# SolarSenseBoard.net
KiCad netlist of a schematic drawn in Altium Designer
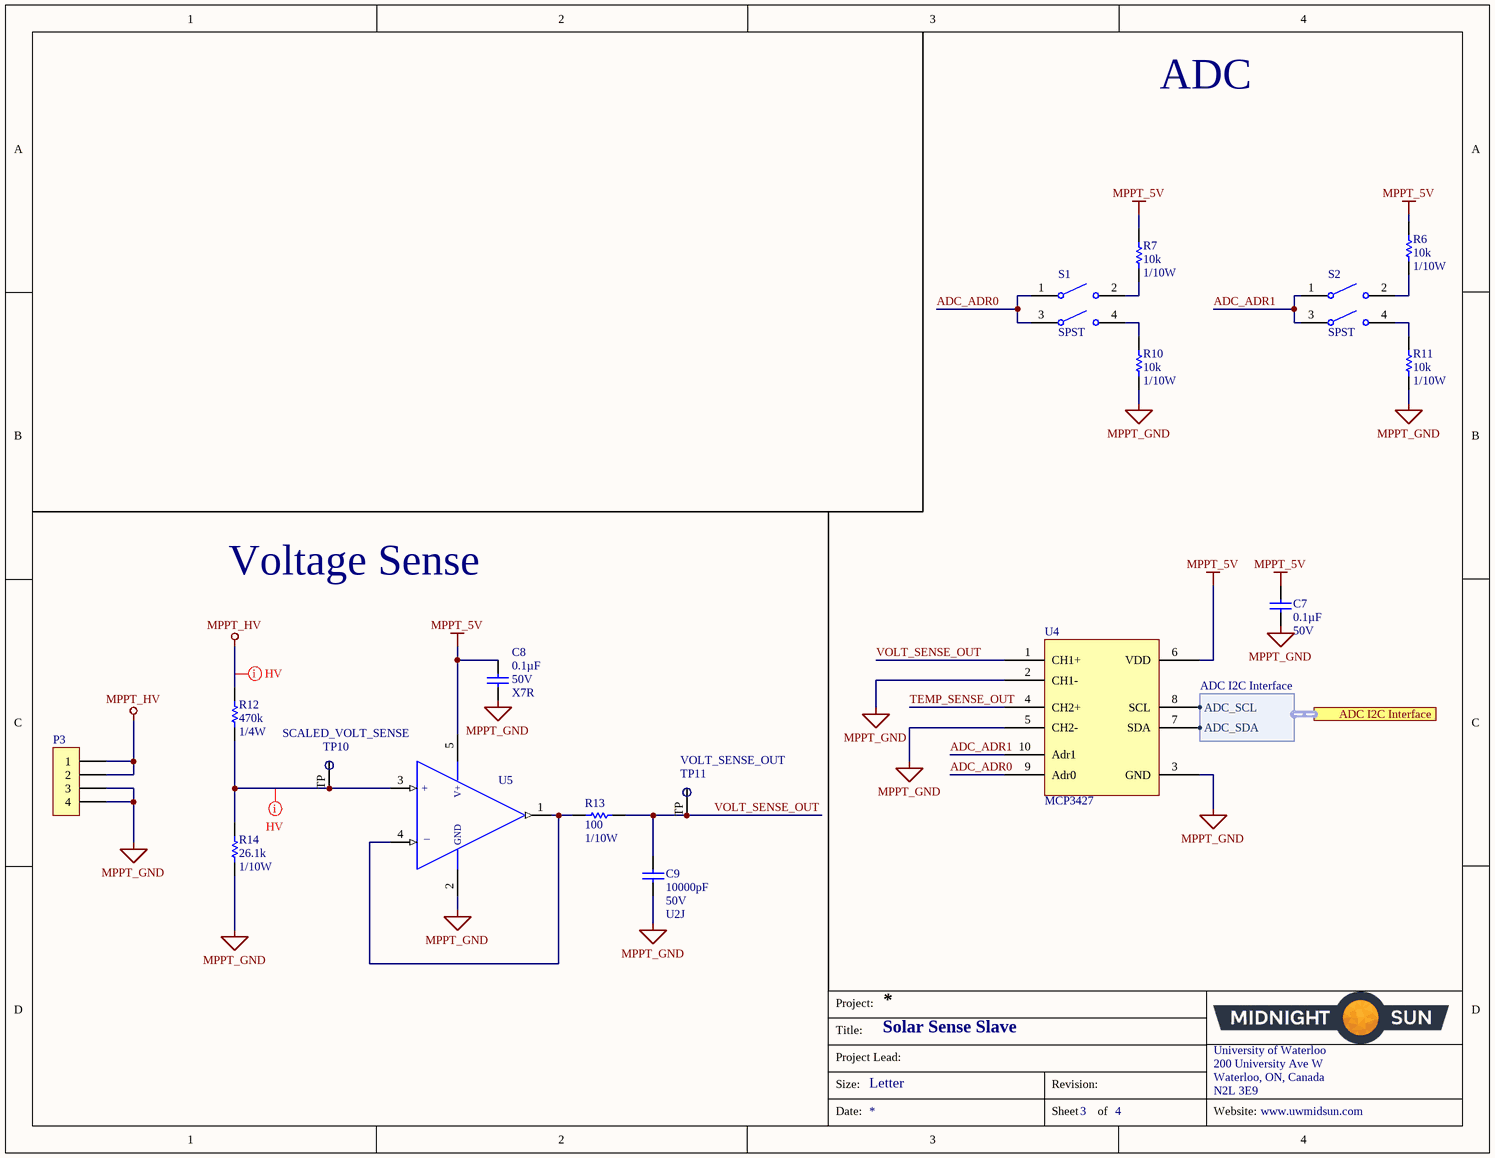
[diagram p0: SolarSenseBoard.SchDoc]

(export (version "E")
  (design (tool "Eeschema 10.0.6"))
  (components
    (comp (ref "C7")
      (value "CAP CER 0.1UF 50V 10% X7R 0603")
      (footprint "CAP, 0603")
      (description "0.10µF ±10% 50V Ceramic Capacitor X7R 0603 (1608 Metric)")
      (fields
        (field (name "TOLERANCE") "±10%")
        (field (name "CAPACITANCE") "0.1µF")
        (field (name "VOLTAGE") "50V")
      )
      (libsource (lib "Schematic Diagrams") (part "CAP CER 0.1UF 50V 10% X7R 0603"))
    )
    (comp (ref "C8")
      (value "CAP CER 0.1UF 50V 10% X7R 0603")
      (footprint "CAP, 0603")
      (description "0.10µF ±10% 50V Ceramic Capacitor X7R 0603 (1608 Metric)")
      (fields
        (field (name "TOLERANCE") "±10%")
        (field (name "CAPACITANCE") "0.1µF")
        (field (name "VOLTAGE") "50V")
        (field (name "TEMPERATURE COEFFICIENT") "X7R")
      )
      (libsource (lib "Schematic Diagrams") (part "CAP CER 0.1UF 50V 10% X7R 0603"))
    )
    (comp (ref "C9")
      (value "CAP CER 10nF 50V 5% X7R 0603")
      (footprint "CAP, 0603")
      (description "10000pF ±5% 50V Ceramic Capacitor U2J 0603 (1608 Metric)")
      (fields
        (field (name "TOLERANCE") "±5%")
        (field (name "CAPACITANCE") "10000pF")
        (field (name "VOLTAGE") "50V")
        (field (name "TEMPERATURE COEFFICIENT") "U2J")
      )
      (libsource (lib "Schematic Diagrams") (part "CAP CER 10nF 50V 5% X7R 0603"))
    )
    (comp (ref "P3")
      (value "CONN 4POS MX150L")
      (footprint "CONN, 4POS MX150L")
      (description "Connector Header Panel Mount, Through Hole, Right Angle 4 position 0.230\" (5.84mm)")
      (libsource (lib "Schematic Diagrams") (part "CONN 4POS MX150L"))
    )
    (comp (ref "R6")
      (value "RES 10K OHM 1% 1/10W 0603")
      (footprint "RES, 0603")
      (description "RES SMD 10K OHM 1% 1/10W 0603")
      (fields
        (field (name "TOLERANCE") "±1%")
        (field (name "RESISTANCE") "10k")
        (field (name "POWER") "1/10W")
      )
      (libsource (lib "Schematic Diagrams") (part "RES 10K OHM 1% 1/10W 0603"))
    )
    (comp (ref "R7")
      (value "RES 10K OHM 1% 1/10W 0603")
      (footprint "RES, 0603")
      (description "RES SMD 10K OHM 1% 1/10W 0603")
      (fields
        (field (name "TOLERANCE") "±1%")
        (field (name "RESISTANCE") "10k")
        (field (name "POWER") "1/10W")
      )
      (libsource (lib "Schematic Diagrams") (part "RES 10K OHM 1% 1/10W 0603"))
    )
    (comp (ref "R10")
      (value "RES 10K OHM 1% 1/10W 0603")
      (footprint "RES, 0603")
      (description "RES SMD 10K OHM 1% 1/10W 0603")
      (fields
        (field (name "TOLERANCE") "±1%")
        (field (name "RESISTANCE") "10k")
        (field (name "POWER") "1/10W")
      )
      (libsource (lib "Schematic Diagrams") (part "RES 10K OHM 1% 1/10W 0603"))
    )
    (comp (ref "R11")
      (value "RES 10K OHM 1% 1/10W 0603")
      (footprint "RES, 0603")
      (description "RES SMD 10K OHM 1% 1/10W 0603")
      (fields
        (field (name "TOLERANCE") "±1%")
        (field (name "RESISTANCE") "10k")
        (field (name "POWER") "1/10W")
      )
      (libsource (lib "Schematic Diagrams") (part "RES 10K OHM 1% 1/10W 0603"))
    )
    (comp (ref "R12")
      (value "RES 470K OHM 1% 1/4W 0603")
      (footprint "RES, 0603")
      (description "RES SMD 470K OHM 1% 1/4W 0603")
      (fields
        (field (name "TOLERANCE") "±1%")
        (field (name "RESISTANCE") "470k")
        (field (name "POWER") "1/4W")
      )
      (libsource (lib "Schematic Diagrams") (part "RES 470K OHM 1% 1/4W 0603"))
    )
    (comp (ref "R13")
      (value "RES 100 OHM 1% 1/10W 0603")
      (footprint "RES, 0603")
      (description "100 Ohm ±1% 0.1W, 1/10W Chip Resistor 0603 (1608 Metric) Moisture Resistant Thick Film")
      (fields
        (field (name "TOLERANCE") "±1%")
        (field (name "RESISTANCE") "100")
        (field (name "POWER") "1/10W")
      )
      (libsource (lib "Schematic Diagrams") (part "RES 100 OHM 1% 1/10W 0603"))
    )
    (comp (ref "R14")
      (value "RES 26.1K OHM 1% 1/10W 0603")
      (footprint "RES, 0603")
      (description "RES SMD 26.1K OHM 1% 1/10W 0603")
      (fields
        (field (name "TOLERANCE") "±1%")
        (field (name "RESISTANCE") "26.1k")
        (field (name "POWER") "1/10W")
      )
      (libsource (lib "Schematic Diagrams") (part "RES 26.1K OHM 1% 1/10W 0603"))
    )
    (comp (ref "S1")
      (value "SPST")
      (footprint "SW SPST 2POS DIP 0.1A 20V")
      (description "SWITCH SLIDE DIP SPST 100MA 20V")
      (fields
        (field (name "MANUFACTURER") "CTS Electrocomponents")
        (field (name "MANUFACTURER PART NUMBER") "219-2MST")
      )
      (libsource (lib "Schematic Diagrams") (part "SW SPST 2POS DIP 0.1A 20V"))
    )
    (comp (ref "S2")
      (value "SPST")
      (footprint "SW SPST 2POS DIP 0.1A 20V")
      (description "SWITCH SLIDE DIP SPST 100MA 20V")
      (fields
        (field (name "MANUFACTURER") "CTS Electrocomponents")
        (field (name "MANUFACTURER PART NUMBER") "219-2MST")
      )
      (libsource (lib "Schematic Diagrams") (part "SW SPST 2POS DIP 0.1A 20V"))
    )
    (comp (ref "TP10")
      (value "SCALED_VOLT_SENSE")
      (footprint "Test Point")
      (libsource (lib "Schematic Diagrams") (part "Test Point"))
    )
    (comp (ref "TP11")
      (value "VOLT_SENSE_OUT")
      (footprint "Test Point")
      (libsource (lib "Schematic Diagrams") (part "Test Point"))
    )
    (comp (ref "U4")
      (value "IC ADC MCP3427 10MSOP")
      (footprint "IC ADC MCP3427")
      (description "16 Bit Analog to Digital Converter 2 Input 1 Sigma-Delta 10-MSOP")
      (fields
        (field (name "MANUFACTURER") "Microchip Technology")
        (field (name "MANUFACTURER PART NUMBER") "MCP3427-E/UN")
        (field (name "BASE PART NUMBER") "MCP3427")
      )
      (libsource (lib "Schematic Diagrams") (part "IC ADC MCP3427 10MSOP"))
    )
    (comp (ref "U5")
      (value "IC OP AMP GEN PURPOSE RR 10MHZ SOT-23-5")
      (footprint "IC OP AMP GP RR 10MHZ SOT-23-5")
      (description "General Purpose Amplifier 1 Circuit Rail-to-Rail SOT-23-5")
      (libsource (lib "Schematic Diagrams") (part "IC OP AMP GEN PURPOSE RR 10MHZ SOT-23-5"))
    )
  )
  (nets
    (net (code "4") (name "/ADC_ADR0") (class "Default")
      (node (ref "S1") (pin "1") (pinfunction "1_1") (pintype "passive"))
      (node (ref "S1") (pin "3") (pinfunction "3_3") (pintype "passive"))
      (node (ref "U4") (pin "9") (pinfunction "Adr0_9") (pintype "passive"))
    )
    (net (code "5") (name "/ADC_ADR1") (class "Default")
      (node (ref "S2") (pin "1") (pinfunction "1_1") (pintype "passive"))
      (node (ref "S2") (pin "3") (pinfunction "3_3") (pintype "passive"))
      (node (ref "U4") (pin "10") (pinfunction "Adr1_10") (pintype "passive"))
    )
    (net (code "6") (name "/ADC_SCL") (class "Default")
      (node (ref "U4") (pin "8") (pinfunction "SCL_8") (pintype "passive"))
    )
    (net (code "7") (name "/ADC_SDA") (class "Default")
      (node (ref "U4") (pin "7") (pinfunction "SDA_7") (pintype "passive"))
    )
    (net (code "8") (name "/TEMP_SENSE_OUT") (class "Default")
      (node (ref "U4") (pin "4") (pinfunction "CH2+_4") (pintype "passive"))
    )
    (net (code "9") (name "/VOLT_SENSE_OUT") (class "Default")
      (node (ref "C9") (pin "1") (pinfunction "1_1") (pintype "passive"))
      (node (ref "R13") (pin "2") (pinfunction "2_2") (pintype "passive"))
      (node (ref "TP11") (pin "TP") (pinfunction "1_TP") (pintype "passive"))
      (node (ref "U4") (pin "1") (pinfunction "CH1+_1") (pintype "passive"))
    )
    (net (code "11") (name "MPPT_5V") (class "Default")
      (node (ref "C7") (pin "1") (pinfunction "1_1") (pintype "passive"))
      (node (ref "C8") (pin "1") (pinfunction "1_1") (pintype "passive"))
      (node (ref "R6") (pin "1") (pinfunction "1_1") (pintype "passive"))
      (node (ref "R7") (pin "1") (pinfunction "1_1") (pintype "passive"))
      (node (ref "U4") (pin "6") (pinfunction "VDD_6") (pintype "passive"))
      (node (ref "U5") (pin "5") (pinfunction "VDD_5") (pintype "power_in"))
    )
    (net (code "12") (name "MPPT_GND") (class "Default")
      (node (ref "C7") (pin "2") (pinfunction "2_2") (pintype "passive"))
      (node (ref "C8") (pin "2") (pinfunction "2_2") (pintype "passive"))
      (node (ref "C9") (pin "2") (pinfunction "2_2") (pintype "passive"))
      (node (ref "P3") (pin "3") (pinfunction "3_3") (pintype "passive"))
      (node (ref "P3") (pin "4") (pinfunction "4_4") (pintype "passive"))
      (node (ref "R10") (pin "2") (pinfunction "2_2") (pintype "passive"))
      (node (ref "R11") (pin "2") (pinfunction "2_2") (pintype "passive"))
      (node (ref "R14") (pin "2") (pinfunction "2_2") (pintype "passive"))
      (node (ref "U4") (pin "2") (pinfunction "CH1-_2") (pintype "passive"))
      (node (ref "U4") (pin "3") (pinfunction "GND_3") (pintype "passive"))
      (node (ref "U4") (pin "5") (pinfunction "CH2-_5") (pintype "passive"))
      (node (ref "U5") (pin "2") (pinfunction "VSS_2") (pintype "power_in"))
    )
    (net (code "13") (name "MPPT_HV") (class "Default")
      (node (ref "P3") (pin "1") (pinfunction "1_1") (pintype "passive"))
      (node (ref "P3") (pin "2") (pinfunction "2_2") (pintype "passive"))
      (node (ref "R12") (pin "1") (pinfunction "1_1") (pintype "passive"))
    )
    (net (code "14") (name "Net-(R6-Pad2)") (class "Default")
      (node (ref "R6") (pin "2") (pinfunction "2_2") (pintype "passive"))
      (node (ref "S2") (pin "2") (pinfunction "2_2") (pintype "passive"))
    )
    (net (code "15") (name "Net-(R7-Pad2)") (class "Default")
      (node (ref "R7") (pin "2") (pinfunction "2_2") (pintype "passive"))
      (node (ref "S1") (pin "2") (pinfunction "2_2") (pintype "passive"))
    )
    (net (code "16") (name "Net-(R10-Pad1)") (class "Default")
      (node (ref "R10") (pin "1") (pinfunction "1_1") (pintype "passive"))
      (node (ref "S1") (pin "4") (pinfunction "4_4") (pintype "passive"))
    )
    (net (code "17") (name "Net-(R11-Pad1)") (class "Default")
      (node (ref "R11") (pin "1") (pinfunction "1_1") (pintype "passive"))
      (node (ref "S2") (pin "4") (pinfunction "4_4") (pintype "passive"))
    )
    (net (code "18") (name "Net-(TP10-1)") (class "Default")
      (node (ref "R12") (pin "2") (pinfunction "2_2") (pintype "passive"))
      (node (ref "R14") (pin "1") (pinfunction "1_1") (pintype "passive"))
      (node (ref "TP10") (pin "TP") (pinfunction "1_TP") (pintype "passive"))
      (node (ref "U5") (pin "3") (pinfunction "+IN_3") (pintype "input"))
    )
    (net (code "19") (name "Net-(U5--IN)") (class "Default")
      (node (ref "R13") (pin "1") (pinfunction "1_1") (pintype "passive"))
      (node (ref "U5") (pin "1") (pinfunction "OUTPUT_1") (pintype "output"))
      (node (ref "U5") (pin "4") (pinfunction "-IN_4") (pintype "input"))
    )
  )
)
